# AVRDevBoard.net
KiCad netlist of a schematic drawn in Altium Designer
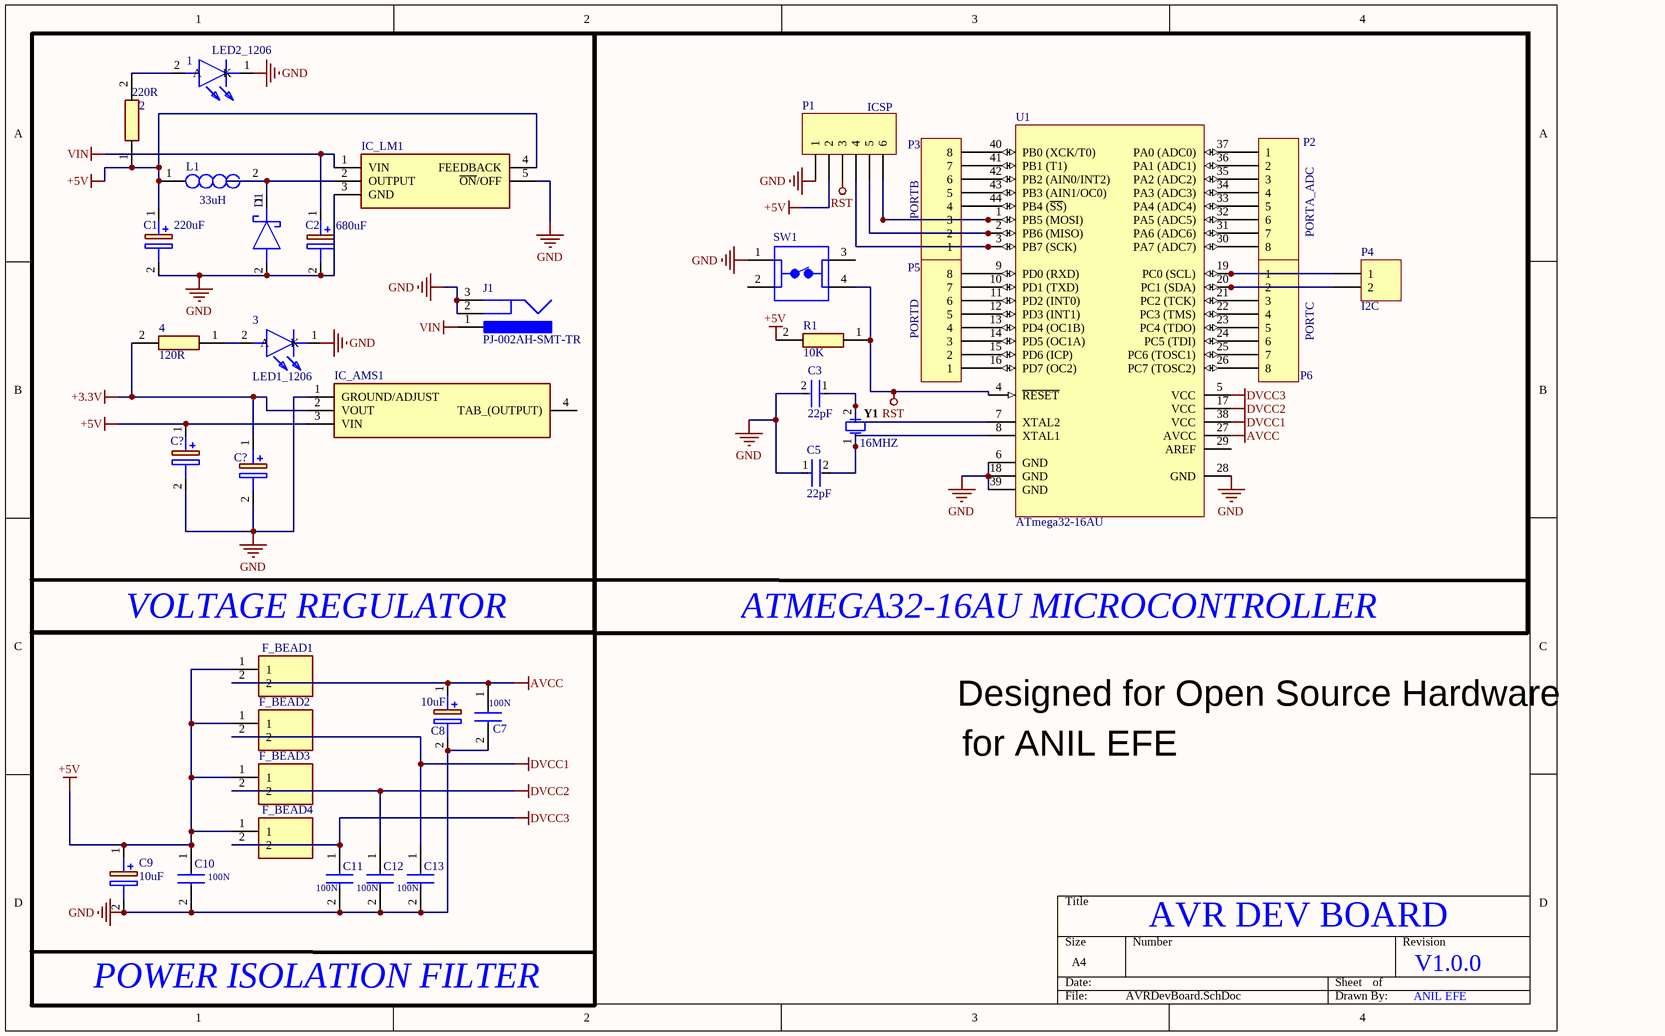
[diagram p0: AVRDevBoard.SchDoc]

(export (version "E")
  (design (tool "Eeschema 10.0.6"))
  (components
    (comp (ref "1")
      (value "LED2_1206")
      (footprint "SamacSys:LEDC3216X130N")
      (description "LED")
      (fields
        (field (name "MANUFACTURER_PART_NUMBER") "QTLP650C2TR")
        (field (name "MOUSER PART NUMBER") "638-QTLP650C2")
      )
      (libsource (lib "*") (part "QTLP650C2TR"))
    )
    (comp (ref "2")
      (value "220R")
      (footprint "SamacSys:RESC3216X70N")
      (description "Resistor")
      (fields
        (field (name "MANUFACTURER_PART_NUMBER") "ERJ-U08F2200V")
        (field (name "MOUSER PART NUMBER") "667-ERJ-U08F2200V")
      )
      (libsource (lib "") (part "ERJ-U08F2200V_1"))
    )
    (comp (ref "3")
      (value "LED1_1206")
      (footprint "SamacSys:LEDC3216X130N")
      (description "LED")
      (fields
        (field (name "MANUFACTURER_PART_NUMBER") "QTLP650C2TR")
        (field (name "MOUSER PART NUMBER") "638-QTLP650C2")
      )
      (libsource (lib "*") (part "QTLP650C2TR"))
    )
    (comp (ref "4")
      (value "120R")
      (footprint "SamacSys:RESC3216X70N")
      (description "Resistor")
      (fields
        (field (name "MANUFACTURER_PART_NUMBER") "ERJ-U08F2200V")
        (field (name "MOUSER PART NUMBER") "667-ERJ-U08F2200V")
      )
      (libsource (lib "*") (part "ERJ-U08F2200V"))
    )
    (comp (ref "C1")
      (value "220uF")
      (footprint "SamacSys:CAPPRD500W65D1250H2200")
      (description "Capacitor Polarised")
      (fields
        (field (name "MANUFACTURER_PART_NUMBER") "EEU-FC1J221S")
        (field (name "MOUSER PART NUMBER") "667-EEU-FC1J221S")
      )
      (libsource (lib "*") (part "EEU-FC1J221S"))
    )
    (comp (ref "C2")
      (value "680uF")
      (footprint "SamacSys:CAPPRD500W60D1275H2200")
      (description "Capacitor Polarised")
      (fields
        (field (name "MANUFACTURER_PART_NUMBER") "UPW1V681MHD")
        (field (name "MOUSER PART NUMBER") "647-UPW1V681MHD")
      )
      (libsource (lib "*") (part "UPW1V681MHD"))
    )
    (comp (ref "C3")
      (value "22pF")
      (footprint "FP-C1206C-EB-MFG")
      (description "1206 22pF Ceramic Multilayer Capacitor; 50VDC; 125degC; C0G Dielec; +/-5% SMD")
      (fields
        (field (name "OCTOPART") "https://octopart.com/c1206c220j5gactu-kemet-131912")
        (field (name "TOLERANCE") "0.05")
      )
      (libsource (lib "Altium Content Vault") (part "b4654b650e69147ec39a6b967a45e02"))
    )
    (comp (ref "C4")
      (value "C?")
      (footprint "SamacSys:CAPPM3528X210N")
      (description "Capacitor Polarised")
      (fields
        (field (name "MANUFACTURER_PART_NUMBER") "TAJB106M025RNJ")
        (field (name "MOUSER PART NUMBER") "581-TAJB106M025RNJ")
      )
      (libsource (lib "*") (part "TAJB106M025RNJ"))
    )
    (comp (ref "C5")
      (value "22pF")
      (footprint "FP-C1206C-EB-MFG")
      (description "1206 22pF Ceramic Multilayer Capacitor; 50VDC; 125degC; C0G Dielec; +/-5% SMD")
      (fields
        (field (name "OCTOPART") "https://octopart.com/c1206c220j5gactu-kemet-131912")
        (field (name "TOLERANCE") "0.05")
      )
      (libsource (lib "Altium Content Vault") (part "b4654b650e69147ec39a6b967a45e02"))
    )
    (comp (ref "C6")
      (value "C?")
      (footprint "SamacSys:CAPPM3528X210N")
      (description "Capacitor Polarised")
      (fields
        (field (name "MANUFACTURER_PART_NUMBER") "TAJB106M025RNJ")
        (field (name "MOUSER PART NUMBER") "581-TAJB106M025RNJ")
      )
      (libsource (lib "*") (part "TAJB106M025RNJ"))
    )
    (comp (ref "C7")
      (value "100N")
      (footprint "SamacSys:CAPC3216X100N")
      (description "Capacitor")
      (fields
        (field (name "MANUFACTURER_PART_NUMBER") "CL31B104KBCNNNC")
        (field (name "RS PART NUMBER") "7666947")
      )
      (libsource (lib "*") (part "CL31B104KBCNNNC"))
    )
    (comp (ref "C8")
      (value "10uF")
      (footprint "SamacSys:CAPPRD200W50D525H1250")
      (description "Capacitor Polarised")
      (fields
        (field (name "MANUFACTURER_PART_NUMBER") "UHE1H100MDD1TD")
        (field (name "MOUSER PART NUMBER") "647-UHE1H100MDD1TD")
      )
      (libsource (lib "*") (part "UHE1H100MDD1TD"))
    )
    (comp (ref "C9")
      (value "10uF")
      (footprint "SamacSys:CAPPRD200W50D525H1250")
      (description "Capacitor Polarised")
      (fields
        (field (name "MANUFACTURER_PART_NUMBER") "UHE1H100MDD1TD")
        (field (name "MOUSER PART NUMBER") "647-UHE1H100MDD1TD")
      )
      (libsource (lib "*") (part "UHE1H100MDD1TD"))
    )
    (comp (ref "C10")
      (value "100N")
      (footprint "SamacSys:CAPC3216X100N")
      (description "Capacitor")
      (fields
        (field (name "MANUFACTURER_PART_NUMBER") "CL31B104KBCNNNC")
        (field (name "RS PART NUMBER") "7666947")
      )
      (libsource (lib "*") (part "CL31B104KBCNNNC"))
    )
    (comp (ref "C11")
      (value "100N")
      (footprint "SamacSys:CAPC3216X100N")
      (description "Capacitor")
      (fields
        (field (name "MANUFACTURER_PART_NUMBER") "CL31B104KBCNNNC")
        (field (name "RS PART NUMBER") "7666947")
      )
      (libsource (lib "*") (part "CL31B104KBCNNNC"))
    )
    (comp (ref "C12")
      (value "100N")
      (footprint "SamacSys:CAPC3216X100N")
      (description "Capacitor")
      (fields
        (field (name "MANUFACTURER_PART_NUMBER") "CL31B104KBCNNNC")
        (field (name "RS PART NUMBER") "7666947")
      )
      (libsource (lib "*") (part "CL31B104KBCNNNC"))
    )
    (comp (ref "C13")
      (value "100N")
      (footprint "SamacSys:CAPC3216X100N")
      (description "Capacitor")
      (fields
        (field (name "MANUFACTURER_PART_NUMBER") "CL31B104KBCNNNC")
        (field (name "RS PART NUMBER") "7666947")
      )
      (libsource (lib "*") (part "CL31B104KBCNNNC"))
    )
    (comp (ref "D1")
      (value "~")
      (footprint "SamacSys:SODFL4725X110N")
      (description "Schottky Diode")
      (fields
        (field (name "MANUFACTURER_PART_NUMBER") "VSS8D5M10-M3/H")
        (field (name "MOUSER PART NUMBER") "78-VSS8D5M10-M3/H")
      )
      (libsource (lib "*") (part "VSS8D5M10-M3_H"))
    )
    (comp (ref "F_BEAD1")
      (value "~")
      (footprint "SamacSys:BEADC3216X180N")
      (description "Filter")
      (fields
        (field (name "MANUFACTURER_PART_NUMBER") "BLM31KN601BH1L")
        (field (name "MOUSER PART NUMBER") "81-BLM31KN601BH1L")
      )
      (libsource (lib "*") (part "BLM31KN601BH1L"))
    )
    (comp (ref "F_BEAD2")
      (value "~")
      (footprint "SamacSys:BEADC3216X180N")
      (description "Filter")
      (fields
        (field (name "MANUFACTURER_PART_NUMBER") "BLM31KN601BH1L")
        (field (name "MOUSER PART NUMBER") "81-BLM31KN601BH1L")
      )
      (libsource (lib "*") (part "BLM31KN601BH1L"))
    )
    (comp (ref "F_BEAD3")
      (value "~")
      (footprint "SamacSys:BEADC3216X180N")
      (description "Filter")
      (fields
        (field (name "MANUFACTURER_PART_NUMBER") "BLM31KN601BH1L")
        (field (name "MOUSER PART NUMBER") "81-BLM31KN601BH1L")
      )
      (libsource (lib "*") (part "BLM31KN601BH1L"))
    )
    (comp (ref "F_BEAD4")
      (value "~")
      (footprint "SamacSys:BEADC3216X180N")
      (description "Filter")
      (fields
        (field (name "MANUFACTURER_PART_NUMBER") "BLM31KN601BH1L")
        (field (name "MOUSER PART NUMBER") "81-BLM31KN601BH1L")
      )
      (libsource (lib "*") (part "BLM31KN601BH1L"))
    )
    (comp (ref "IC_AMS1")
      (value "~")
      (footprint "SamacSys:SOT229P700X180-4N")
      (description "Integrated Circuit")
      (fields (field (name "MANUFACTURER_PART_NUMBER") "ams1117-3.3v"))
      (libsource (lib "*") (part "ams1117-3.3v"))
    )
    (comp (ref "IC_LM1")
      (value "~")
      (footprint "SamacSys:TO170P470X1028X2142-5P")
      (description "Integrated Circuit")
      (fields
        (field (name "MANUFACTURER_PART_NUMBER") "LM2596T-5.0")
        (field (name "MOUSER PART NUMBER") "926-LM2596T-50")
      )
      (libsource (lib "*") (part "LM2596T-5.0"))
    )
    (comp (ref "J1")
      (value "PJ-002AH-SMT-TR")
      (footprint "CUI-PJ-002AH-4_V")
      (description "DC Power Jack, Right Angle, -25 to 85 degC, 4-Pin 14.8 x 9 x 11 mm SMD, RoHS, Tape and Reel")
      (fields (field (name "MANUFACTURER") "CUIInc.") (field (name "PARTNUMBER") "PJ-002AH"))
      (libsource (lib "Altium Content Vault") (part "JACK-2CD3-RN"))
    )
    (comp (ref "L1")
      (value "33uH")
      (footprint "SamacSys:INDPM6063X300N")
      (description "Inductor")
      (fields
        (field (name "MANUFACTURER_PART_NUMBER") "B82462G4333M000")
        (field (name "MOUSER PART NUMBER") "871-B82462G4333M")
      )
      (libsource (lib "*") (part "B82462G4333M000"))
    )
    (comp (ref "P1")
      (value "ICSP")
      (footprint "HDR1X6")
      (description "Header, 6-Pin")
      (fields (field (name "PUBLISHER") "Altium Limited"))
      (libsource (lib "Miscellaneous Connectors") (part "Header 6"))
    )
    (comp (ref "P2")
      (value "PORTA_ADC")
      (footprint "HDR1X8")
      (description "Header, 8-Pin")
      (fields (field (name "PUBLISHER") "Altium Limited"))
      (libsource (lib "Miscellaneous Connectors") (part "Header 8"))
    )
    (comp (ref "P3")
      (value "PORTB")
      (footprint "HDR1X8")
      (description "Header, 8-Pin")
      (fields (field (name "PUBLISHER") "Altium Limited"))
      (libsource (lib "") (part "Header 8_1"))
    )
    (comp (ref "P4")
      (value "I2C")
      (footprint "HDR1X2")
      (description "Header, 2-Pin")
      (fields (field (name "PUBLISHER") "Altium Limited"))
      (libsource (lib "Miscellaneous Connectors") (part "Header 2"))
    )
    (comp (ref "P5")
      (value "PORTD")
      (footprint "HDR1X8")
      (description "Header, 8-Pin")
      (fields (field (name "PUBLISHER") "Altium Limited"))
      (libsource (lib "") (part "Header 8_1"))
    )
    (comp (ref "P6")
      (value "PORTC")
      (footprint "HDR1X8")
      (description "Header, 8-Pin")
      (fields (field (name "PUBLISHER") "Altium Limited"))
      (libsource (lib "Miscellaneous Connectors") (part "Header 8"))
    )
    (comp (ref "R1")
      (value "10K")
      (footprint "SamacSys:RESC3216X70N")
      (description "Resistor")
      (fields
        (field (name "MANUFACTURER_PART_NUMBER") "ERJ-U08F2200V")
        (field (name "MOUSER PART NUMBER") "667-ERJ-U08F2200V")
      )
      (libsource (lib "*") (part "ERJ-U08F2200V"))
    )
    (comp (ref "SW1")
      (value "~")
      (footprint "SnapEDApcb:TE_3-1825910-1")
      (description "Switch Push Button OFF _ON_ SPST Round Button 0.05A 24VDC Momentary Contact PC Pins Thru-Hole")
      (fields (field (name "MF") "TE Connectivity") (field (name "MP") "3-1825910-1"))
      (libsource (lib "SnapEDAsch") (part "3-1825910-1"))
    )
    (comp (ref "U1")
      (value "ATmega32-16AU")
      (footprint "44A_N")
      (libsource (lib "Altium Content Vault") (part "MC-8B-ATM32-SQ44"))
    )
    (comp (ref "Y1")
      (value "16MHZ")
      (footprint "FOX-FOXSLF160-20")
      (description "Resistance Weld Thru-Hole Crystal, 16 MHz, -20 to 70 degC, 2-Pin THD, RoHS, Bulk")
      (fields (field (name "TOLERANCE") "1%"))
      (libsource (lib "Altium Content Vault") (part "XTAL-1-2-2"))
    )
  )
  (nets
    (net (code "1") (name "+3.3V") (class "Default")
      (node (ref "4") (pin "2") (pinfunction "2_2") (pintype "passive"))
      (node (ref "C6") (pin "1") (pinfunction "+_1") (pintype "passive"))
      (node (ref "IC_AMS1") (pin "2") (pinfunction "VOUT_2") (pintype "passive"))
    )
    (net (code "2") (name "+5V") (class "Default")
      (node (ref "2") (pin "1") (pinfunction "1_1") (pintype "passive"))
      (node (ref "C1") (pin "1") (pinfunction "+_1") (pintype "passive"))
      (node (ref "C10") (pin "1") (pinfunction "1_1") (pintype "passive"))
      (node (ref "C4") (pin "1") (pinfunction "+_1") (pintype "passive"))
      (node (ref "C9") (pin "1") (pinfunction "+_1") (pintype "passive"))
      (node (ref "F_BEAD1") (pin "1") (pinfunction "1_1") (pintype "passive"))
      (node (ref "F_BEAD2") (pin "1") (pinfunction "1_1") (pintype "passive"))
      (node (ref "F_BEAD3") (pin "1") (pinfunction "1_1") (pintype "passive"))
      (node (ref "F_BEAD4") (pin "1") (pinfunction "1_1") (pintype "passive"))
      (node (ref "IC_AMS1") (pin "3") (pinfunction "VIN_3") (pintype "passive"))
      (node (ref "IC_LM1") (pin "4") (pinfunction "FEEDBACK_4") (pintype "passive"))
      (node (ref "L1") (pin "1") (pinfunction "1_1") (pintype "passive"))
      (node (ref "P1") (pin "2") (pinfunction "2_2") (pintype "passive"))
      (node (ref "R1") (pin "2") (pinfunction "2_2") (pintype "passive"))
    )
    (net (code "3") (name "AVCC") (class "Default")
      (node (ref "C7") (pin "1") (pinfunction "1_1") (pintype "passive"))
      (node (ref "C8") (pin "1") (pinfunction "+_1") (pintype "passive"))
      (node (ref "F_BEAD1") (pin "2") (pinfunction "2_2") (pintype "passive"))
      (node (ref "U1") (pin "27") (pinfunction "AVCC_27") (pintype "power_in"))
    )
    (net (code "4") (name "DVCC1") (class "Default")
      (node (ref "C13") (pin "1") (pinfunction "1_1") (pintype "passive"))
      (node (ref "F_BEAD2") (pin "2") (pinfunction "2_2") (pintype "passive"))
      (node (ref "U1") (pin "38") (pinfunction "VCC_38") (pintype "power_in"))
    )
    (net (code "5") (name "DVCC2") (class "Default")
      (node (ref "C12") (pin "1") (pinfunction "1_1") (pintype "passive"))
      (node (ref "F_BEAD3") (pin "2") (pinfunction "2_2") (pintype "passive"))
      (node (ref "U1") (pin "17") (pinfunction "VCC_17") (pintype "power_in"))
    )
    (net (code "6") (name "DVCC3") (class "Default")
      (node (ref "C11") (pin "1") (pinfunction "1_1") (pintype "passive"))
      (node (ref "F_BEAD4") (pin "2") (pinfunction "2_2") (pintype "passive"))
      (node (ref "U1") (pin "5") (pinfunction "VCC_5") (pintype "power_in"))
    )
    (net (code "7") (name "GND") (class "Default")
      (node (ref "1") (pin "1") (pinfunction "K_1") (pintype "passive"))
      (node (ref "3") (pin "1") (pinfunction "K_1") (pintype "passive"))
      (node (ref "C1") (pin "2") (pinfunction "-_2") (pintype "passive"))
      (node (ref "C10") (pin "2") (pinfunction "2_2") (pintype "passive"))
      (node (ref "C11") (pin "2") (pinfunction "2_2") (pintype "passive"))
      (node (ref "C12") (pin "2") (pinfunction "2_2") (pintype "passive"))
      (node (ref "C13") (pin "2") (pinfunction "2_2") (pintype "passive"))
      (node (ref "C2") (pin "2") (pinfunction "-_2") (pintype "passive"))
      (node (ref "C3") (pin "2") (pinfunction "2_2") (pintype "passive"))
      (node (ref "C4") (pin "2") (pinfunction "-_2") (pintype "passive"))
      (node (ref "C5") (pin "1") (pinfunction "1_1") (pintype "passive"))
      (node (ref "C6") (pin "2") (pinfunction "-_2") (pintype "passive"))
      (node (ref "C7") (pin "2") (pinfunction "2_2") (pintype "passive"))
      (node (ref "C8") (pin "2") (pinfunction "-_2") (pintype "passive"))
      (node (ref "C9") (pin "2") (pinfunction "-_2") (pintype "passive"))
      (node (ref "D1") (pin "2") (pinfunction "A_2") (pintype "passive"))
      (node (ref "IC_AMS1") (pin "1") (pinfunction "GROUND/ADJUST_1") (pintype "passive"))
      (node (ref "IC_LM1") (pin "3") (pinfunction "GND_3") (pintype "passive"))
      (node (ref "IC_LM1") (pin "5") (pinfunction "~{ON}/OFF_5") (pintype "passive"))
      (node (ref "J1") (pin "2") (pinfunction "2_2") (pintype "passive"))
      (node (ref "J1") (pin "3") (pinfunction "3_3") (pintype "passive"))
      (node (ref "P1") (pin "1") (pinfunction "1_1") (pintype "passive"))
      (node (ref "SW1") (pin "1") (pinfunction "1_1") (pintype "passive"))
      (node (ref "U1") (pin "18") (pinfunction "GND_18") (pintype "power_in"))
      (node (ref "U1") (pin "28") (pinfunction "GND_28") (pintype "power_in"))
      (node (ref "U1") (pin "39") (pinfunction "GND_39") (pintype "power_in"))
      (node (ref "U1") (pin "6") (pinfunction "GND_6") (pintype "power_in"))
    )
    (net (code "8") (name "Net-(1-A)") (class "Default")
      (node (ref "1") (pin "2") (pinfunction "A_2") (pintype "passive"))
      (node (ref "2") (pin "2") (pinfunction "2_2") (pintype "passive"))
    )
    (net (code "9") (name "Net-(3-A)") (class "Default")
      (node (ref "3") (pin "2") (pinfunction "A_2") (pintype "passive"))
      (node (ref "4") (pin "1") (pinfunction "1_1") (pintype "passive"))
    )
    (net (code "10") (name "Net-(D1-K)") (class "Default")
      (node (ref "D1") (pin "1") (pinfunction "K_1") (pintype "passive"))
      (node (ref "IC_LM1") (pin "2") (pinfunction "OUTPUT_2") (pintype "passive"))
      (node (ref "L1") (pin "2") (pinfunction "2_2") (pintype "passive"))
    )
    (net (code "11") (name "Net-(U1-PA0_(ADC0))") (class "Default")
      (node (ref "P2") (pin "1") (pinfunction "1_1") (pintype "passive"))
      (node (ref "U1") (pin "37") (pinfunction "PA0_(ADC0)_37") (pintype "bidirectional"))
    )
    (net (code "12") (name "Net-(U1-PA1_(ADC1))") (class "Default")
      (node (ref "P2") (pin "2") (pinfunction "2_2") (pintype "passive"))
      (node (ref "U1") (pin "36") (pinfunction "PA1_(ADC1)_36") (pintype "bidirectional"))
    )
    (net (code "13") (name "Net-(U1-PA2_(ADC2))") (class "Default")
      (node (ref "P2") (pin "3") (pinfunction "3_3") (pintype "passive"))
      (node (ref "U1") (pin "35") (pinfunction "PA2_(ADC2)_35") (pintype "bidirectional"))
    )
    (net (code "14") (name "Net-(U1-PA3_(ADC3))") (class "Default")
      (node (ref "P2") (pin "4") (pinfunction "4_4") (pintype "passive"))
      (node (ref "U1") (pin "34") (pinfunction "PA3_(ADC3)_34") (pintype "bidirectional"))
    )
    (net (code "15") (name "Net-(U1-PA4_(ADC4))") (class "Default")
      (node (ref "P2") (pin "5") (pinfunction "5_5") (pintype "passive"))
      (node (ref "U1") (pin "33") (pinfunction "PA4_(ADC4)_33") (pintype "bidirectional"))
    )
    (net (code "16") (name "Net-(U1-PA5_(ADC5))") (class "Default")
      (node (ref "P2") (pin "6") (pinfunction "6_6") (pintype "passive"))
      (node (ref "U1") (pin "32") (pinfunction "PA5_(ADC5)_32") (pintype "bidirectional"))
    )
    (net (code "17") (name "Net-(U1-PA6_(ADC6))") (class "Default")
      (node (ref "P2") (pin "7") (pinfunction "7_7") (pintype "passive"))
      (node (ref "U1") (pin "31") (pinfunction "PA6_(ADC6)_31") (pintype "bidirectional"))
    )
    (net (code "18") (name "Net-(U1-PA7_(ADC7))") (class "Default")
      (node (ref "P2") (pin "8") (pinfunction "8_8") (pintype "passive"))
      (node (ref "U1") (pin "30") (pinfunction "PA7_(ADC7)_30") (pintype "bidirectional"))
    )
    (net (code "19") (name "Net-(U1-PB0_(XCK{slash}T0))") (class "Default")
      (node (ref "P3") (pin "8") (pinfunction "8_8") (pintype "passive"))
      (node (ref "U1") (pin "40") (pinfunction "PB0_(XCK/T0)_40") (pintype "bidirectional"))
    )
    (net (code "20") (name "Net-(U1-PB1_(T1))") (class "Default")
      (node (ref "P3") (pin "7") (pinfunction "7_7") (pintype "passive"))
      (node (ref "U1") (pin "41") (pinfunction "PB1_(T1)_41") (pintype "bidirectional"))
    )
    (net (code "21") (name "Net-(U1-PB2_(AIN0{slash}INT2))") (class "Default")
      (node (ref "P3") (pin "6") (pinfunction "6_6") (pintype "passive"))
      (node (ref "U1") (pin "42") (pinfunction "PB2_(AIN0/INT2)_42") (pintype "bidirectional"))
    )
    (net (code "22") (name "Net-(U1-PB3_(AIN1{slash}OC0))") (class "Default")
      (node (ref "P3") (pin "5") (pinfunction "5_5") (pintype "passive"))
      (node (ref "U1") (pin "43") (pinfunction "PB3_(AIN1/OC0)_43") (pintype "bidirectional"))
    )
    (net (code "23") (name "Net-(U1-PB4_(~{SS}))") (class "Default")
      (node (ref "P3") (pin "4") (pinfunction "4_4") (pintype "passive"))
      (node (ref "U1") (pin "44") (pinfunction "PB4_(~{SS})_44") (pintype "bidirectional"))
    )
    (net (code "24") (name "Net-(U1-PB5_(MOSI))") (class "Default")
      (node (ref "P1") (pin "6") (pinfunction "6_6") (pintype "passive"))
      (node (ref "P3") (pin "3") (pinfunction "3_3") (pintype "passive"))
      (node (ref "U1") (pin "1") (pinfunction "PB5_(MOSI)_1") (pintype "bidirectional"))
    )
    (net (code "25") (name "Net-(U1-PB6_(MISO))") (class "Default")
      (node (ref "P1") (pin "5") (pinfunction "5_5") (pintype "passive"))
      (node (ref "P3") (pin "2") (pinfunction "2_2") (pintype "passive"))
      (node (ref "U1") (pin "2") (pinfunction "PB6_(MISO)_2") (pintype "bidirectional"))
    )
    (net (code "26") (name "Net-(U1-PB7_(SCK))") (class "Default")
      (node (ref "P1") (pin "4") (pinfunction "4_4") (pintype "passive"))
      (node (ref "P3") (pin "1") (pinfunction "1_1") (pintype "passive"))
      (node (ref "U1") (pin "3") (pinfunction "PB7_(SCK)_3") (pintype "bidirectional"))
    )
    (net (code "27") (name "Net-(U1-PC0_(SCL))") (class "Default")
      (node (ref "P4") (pin "1") (pinfunction "1_1") (pintype "passive"))
      (node (ref "P6") (pin "1") (pinfunction "1_1") (pintype "passive"))
      (node (ref "U1") (pin "19") (pinfunction "PC0_(SCL)_19") (pintype "bidirectional"))
    )
    (net (code "28") (name "Net-(U1-PC1_(SDA))") (class "Default")
      (node (ref "P4") (pin "2") (pinfunction "2_2") (pintype "passive"))
      (node (ref "P6") (pin "2") (pinfunction "2_2") (pintype "passive"))
      (node (ref "U1") (pin "20") (pinfunction "PC1_(SDA)_20") (pintype "bidirectional"))
    )
    (net (code "29") (name "Net-(U1-PC2_(TCK))") (class "Default")
      (node (ref "P6") (pin "3") (pinfunction "3_3") (pintype "passive"))
      (node (ref "U1") (pin "21") (pinfunction "PC2_(TCK)_21") (pintype "bidirectional"))
    )
    (net (code "30") (name "Net-(U1-PC3_(TMS))") (class "Default")
      (node (ref "P6") (pin "4") (pinfunction "4_4") (pintype "passive"))
      (node (ref "U1") (pin "22") (pinfunction "PC3_(TMS)_22") (pintype "bidirectional"))
    )
    (net (code "31") (name "Net-(U1-PC4_(TDO))") (class "Default")
      (node (ref "P6") (pin "5") (pinfunction "5_5") (pintype "passive"))
      (node (ref "U1") (pin "23") (pinfunction "PC4_(TDO)_23") (pintype "bidirectional"))
    )
    (net (code "32") (name "Net-(U1-PC5_(TDI))") (class "Default")
      (node (ref "P6") (pin "6") (pinfunction "6_6") (pintype "passive"))
      (node (ref "U1") (pin "24") (pinfunction "PC5_(TDI)_24") (pintype "bidirectional"))
    )
    (net (code "33") (name "Net-(U1-PC6_(TOSC1))") (class "Default")
      (node (ref "P6") (pin "7") (pinfunction "7_7") (pintype "passive"))
      (node (ref "U1") (pin "25") (pinfunction "PC6_(TOSC1)_25") (pintype "bidirectional"))
    )
    (net (code "34") (name "Net-(U1-PC7_(TOSC2))") (class "Default")
      (node (ref "P6") (pin "8") (pinfunction "8_8") (pintype "passive"))
      (node (ref "U1") (pin "26") (pinfunction "PC7_(TOSC2)_26") (pintype "bidirectional"))
    )
    (net (code "35") (name "Net-(U1-PD0_(RXD))") (class "Default")
      (node (ref "P5") (pin "8") (pinfunction "8_8") (pintype "passive"))
      (node (ref "U1") (pin "9") (pinfunction "PD0_(RXD)_9") (pintype "bidirectional"))
    )
    (net (code "36") (name "Net-(U1-PD1_(TXD))") (class "Default")
      (node (ref "P5") (pin "7") (pinfunction "7_7") (pintype "passive"))
      (node (ref "U1") (pin "10") (pinfunction "PD1_(TXD)_10") (pintype "bidirectional"))
    )
    (net (code "37") (name "Net-(U1-PD2_(INT0))") (class "Default")
      (node (ref "P5") (pin "6") (pinfunction "6_6") (pintype "passive"))
      (node (ref "U1") (pin "11") (pinfunction "PD2_(INT0)_11") (pintype "bidirectional"))
    )
    (net (code "38") (name "Net-(U1-PD3_(INT1))") (class "Default")
      (node (ref "P5") (pin "5") (pinfunction "5_5") (pintype "passive"))
      (node (ref "U1") (pin "12") (pinfunction "PD3_(INT1)_12") (pintype "bidirectional"))
    )
    (net (code "39") (name "Net-(U1-PD4_(OC1B))") (class "Default")
      (node (ref "P5") (pin "4") (pinfunction "4_4") (pintype "passive"))
      (node (ref "U1") (pin "13") (pinfunction "PD4_(OC1B)_13") (pintype "bidirectional"))
    )
    (net (code "40") (name "Net-(U1-PD5_(OC1A))") (class "Default")
      (node (ref "P5") (pin "3") (pinfunction "3_3") (pintype "passive"))
      (node (ref "U1") (pin "14") (pinfunction "PD5_(OC1A)_14") (pintype "bidirectional"))
    )
    (net (code "41") (name "Net-(U1-PD6_(ICP))") (class "Default")
      (node (ref "P5") (pin "2") (pinfunction "2_2") (pintype "passive"))
      (node (ref "U1") (pin "15") (pinfunction "PD6_(ICP)_15") (pintype "bidirectional"))
    )
    (net (code "42") (name "Net-(U1-PD7_(OC2))") (class "Default")
      (node (ref "P5") (pin "1") (pinfunction "1_1") (pintype "passive"))
      (node (ref "U1") (pin "16") (pinfunction "PD7_(OC2)_16") (pintype "bidirectional"))
    )
    (net (code "43") (name "Net-(U1-XTAL1)") (class "Default")
      (node (ref "C5") (pin "2") (pinfunction "2_2") (pintype "passive"))
      (node (ref "U1") (pin "8") (pinfunction "XTAL1_8") (pintype "passive"))
      (node (ref "Y1") (pin "1") (pinfunction "1_1") (pintype "passive"))
    )
    (net (code "44") (name "Net-(U1-XTAL2)") (class "Default")
      (node (ref "C3") (pin "1") (pinfunction "1_1") (pintype "passive"))
      (node (ref "U1") (pin "7") (pinfunction "XTAL2_7") (pintype "passive"))
      (node (ref "Y1") (pin "2") (pinfunction "2_2") (pintype "passive"))
    )
    (net (code "45") (name "RST") (class "Default")
      (node (ref "P1") (pin "3") (pinfunction "3_3") (pintype "passive"))
      (node (ref "R1") (pin "1") (pinfunction "1_1") (pintype "passive"))
      (node (ref "SW1") (pin "4") (pinfunction "4_4") (pintype "passive"))
      (node (ref "U1") (pin "4") (pinfunction "~{RESET}_4") (pintype "input"))
    )
    (net (code "46") (name "VIN") (class "Default")
      (node (ref "C2") (pin "1") (pinfunction "+_1") (pintype "passive"))
      (node (ref "IC_LM1") (pin "1") (pinfunction "VIN_1") (pintype "passive"))
      (node (ref "J1") (pin "1") (pinfunction "1_1") (pintype "passive"))
    )
    (net (code "47") (name "unconnected-(IC_AMS1-TAB_(OUTPUT)-Pad4)") (class "Default")
      (node (ref "IC_AMS1") (pin "4") (pinfunction "TAB_(OUTPUT)_4") (pintype "passive"))
    )
    (net (code "48") (name "unconnected-(SW1-Pad2)") (class "Default")
      (node (ref "SW1") (pin "2") (pinfunction "2_2") (pintype "passive"))
    )
    (net (code "49") (name "unconnected-(SW1-Pad3)") (class "Default")
      (node (ref "SW1") (pin "3") (pinfunction "3_3") (pintype "passive"))
    )
    (net (code "50") (name "unconnected-(U1-AREF-Pad29)") (class "Default")
      (node (ref "U1") (pin "29") (pinfunction "AREF_29") (pintype "passive"))
    )
  )
)
